# MT32Pi_Main.net
KiCad netlist of a schematic drawn in Altium Designer
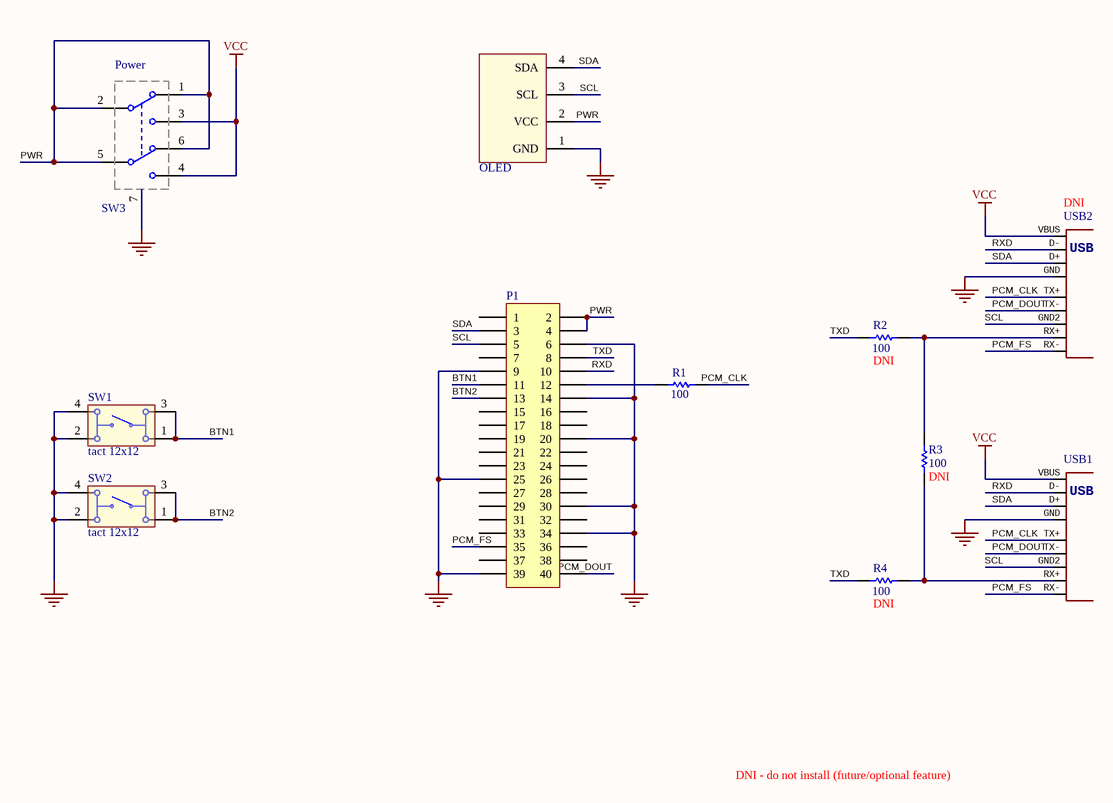
[diagram p0: MT32Pi_Main.SchDoc]

(export (version "E")
  (design (tool "Eeschema 10.0.6"))
  (components
    (comp (ref "OLED")
      (value "OLED")
      (footprint "OLED_128x64")
      (description "OLED 128x84 0.96\"")
      (libsource (lib "lib") (part "OLED"))
    )
    (comp (ref "P1")
      (value "Header 20X2")
      (footprint "HDR20x2")
      (description "Header, 20-Pin, Dual row")
      (fields (field (name "PUBLISHER") "Altium Limited"))
      (libsource (lib "Miscellaneous Connectors") (part "Header 20X2"))
    )
    (comp (ref "R1")
      (value "100")
      (footprint "R0805")
      (fields (field (name "PUBLISHER") "Altium Limited"))
      (libsource (lib "lib") (part "R0805"))
    )
    (comp (ref "R2")
      (value "100")
      (footprint "R0805 - DNI")
      (fields (field (name "PUBLISHER") "Altium Limited"))
      (libsource (lib "lib") (part "R0805 - DNI"))
    )
    (comp (ref "R3")
      (value "100")
      (footprint "R0805 - DNI")
      (fields (field (name "PUBLISHER") "Altium Limited"))
      (libsource (lib "lib") (part "R0805 - DNI"))
    )
    (comp (ref "R4")
      (value "100")
      (footprint "R0805 - DNI")
      (fields (field (name "PUBLISHER") "Altium Limited"))
      (libsource (lib "lib") (part "R0805 - DNI"))
    )
    (comp (ref "SW1")
      (value "tact 12x12")
      (footprint "tact 12x12")
      (libsource (lib "lib") (part "tact 12x12"))
    )
    (comp (ref "SW2")
      (value "tact 12x12")
      (footprint "tact 12x12")
      (libsource (lib "lib") (part "tact 12x12"))
    )
    (comp (ref "SW3") (value "Power") (footprint "SW DPDT") (libsource (lib "lib") (part "SW DPDT")))
    (comp (ref "USB1")
      (value "USBA30-PTH")
      (footprint "USB3-A-F-PTH")
      (fields (field (name "USB") "USB"))
      (libsource (lib "lib") (part "USBA30-PTH"))
    )
    (comp (ref "USB2")
      (value "USBA30-PTH")
      (footprint "USB3-A-F-PTH")
      (fields (field (name "USB") "USB"))
      (libsource (lib "lib") (part "USBA30-PTH"))
    )
  )
  (nets
    (net (code "1") (name "/BTN1") (class "Default")
      (node (ref "P1") (pin "11") (pinfunction "11_11") (pintype "passive"))
      (node (ref "SW1") (pin "1") (pinfunction "1_1") (pintype "passive"))
      (node (ref "SW1") (pin "3") (pinfunction "3_3") (pintype "passive"))
    )
    (net (code "2") (name "/BTN2") (class "Default")
      (node (ref "P1") (pin "13") (pinfunction "13_13") (pintype "passive"))
      (node (ref "SW2") (pin "1") (pinfunction "1_1") (pintype "passive"))
      (node (ref "SW2") (pin "3") (pinfunction "3_3") (pintype "passive"))
    )
    (net (code "3") (name "/PCM_CLK") (class "Default")
      (node (ref "R1") (pin "1") (pinfunction "1_1") (pintype "passive"))
      (node (ref "USB1") (pin "TX+") (pinfunction "TX+_TX+") (pintype "passive"))
      (node (ref "USB2") (pin "TX+") (pinfunction "TX+_TX+") (pintype "passive"))
    )
    (net (code "4") (name "/PCM_DOUT") (class "Default")
      (node (ref "P1") (pin "40") (pinfunction "40_40") (pintype "passive"))
      (node (ref "USB1") (pin "TX-") (pinfunction "TX-_TX-") (pintype "passive"))
      (node (ref "USB2") (pin "TX-") (pinfunction "TX-_TX-") (pintype "passive"))
    )
    (net (code "5") (name "/PCM_FS") (class "Default")
      (node (ref "P1") (pin "35") (pinfunction "35_35") (pintype "passive"))
      (node (ref "USB1") (pin "RX-") (pinfunction "RX-_RX-") (pintype "passive"))
      (node (ref "USB2") (pin "RX-") (pinfunction "RX-_RX-") (pintype "passive"))
    )
    (net (code "6") (name "/PWR") (class "Default")
      (node (ref "OLED") (pin "2") (pinfunction "VCC_2") (pintype "passive"))
      (node (ref "P1") (pin "2") (pinfunction "2_2") (pintype "passive"))
      (node (ref "P1") (pin "4") (pinfunction "4_4") (pintype "passive"))
      (node (ref "SW3") (pin "1") (pinfunction "NC1_1") (pintype "passive"))
      (node (ref "SW3") (pin "2") (pinfunction "COMMON1_2") (pintype "passive"))
      (node (ref "SW3") (pin "5") (pinfunction "COMMON2_5") (pintype "passive"))
      (node (ref "SW3") (pin "6") (pinfunction "NC2_6") (pintype "passive"))
    )
    (net (code "7") (name "/RXD") (class "Default")
      (node (ref "P1") (pin "10") (pinfunction "10_10") (pintype "passive"))
      (node (ref "USB1") (pin "D-") (pinfunction "D-_D-") (pintype "passive"))
      (node (ref "USB2") (pin "D-") (pinfunction "D-_D-") (pintype "passive"))
    )
    (net (code "8") (name "/SCL") (class "Default")
      (node (ref "OLED") (pin "3") (pinfunction "SCL_3") (pintype "passive"))
      (node (ref "P1") (pin "5") (pinfunction "5_5") (pintype "passive"))
      (node (ref "USB1") (pin "GND2") (pinfunction "GND2_GND2") (pintype "passive"))
      (node (ref "USB2") (pin "GND2") (pinfunction "GND2_GND2") (pintype "passive"))
    )
    (net (code "9") (name "/SDA") (class "Default")
      (node (ref "OLED") (pin "4") (pinfunction "SDA_4") (pintype "passive"))
      (node (ref "P1") (pin "3") (pinfunction "3_3") (pintype "passive"))
      (node (ref "USB1") (pin "D+") (pinfunction "D+_D+") (pintype "passive"))
      (node (ref "USB2") (pin "D+") (pinfunction "D+_D+") (pintype "passive"))
    )
    (net (code "10") (name "/TXD") (class "Default")
      (node (ref "P1") (pin "8") (pinfunction "8_8") (pintype "passive"))
      (node (ref "R2") (pin "1") (pinfunction "1_1") (pintype "passive"))
      (node (ref "R4") (pin "1") (pinfunction "1_1") (pintype "passive"))
    )
    (net (code "11") (name "GND") (class "Default")
      (node (ref "OLED") (pin "1") (pinfunction "GND_1") (pintype "passive"))
      (node (ref "P1") (pin "14") (pinfunction "14_14") (pintype "passive"))
      (node (ref "P1") (pin "20") (pinfunction "20_20") (pintype "passive"))
      (node (ref "P1") (pin "25") (pinfunction "25_25") (pintype "passive"))
      (node (ref "P1") (pin "30") (pinfunction "30_30") (pintype "passive"))
      (node (ref "P1") (pin "34") (pinfunction "34_34") (pintype "passive"))
      (node (ref "P1") (pin "39") (pinfunction "39_39") (pintype "passive"))
      (node (ref "P1") (pin "6") (pinfunction "6_6") (pintype "passive"))
      (node (ref "P1") (pin "9") (pinfunction "9_9") (pintype "passive"))
      (node (ref "SW1") (pin "2") (pinfunction "2_2") (pintype "passive"))
      (node (ref "SW1") (pin "4") (pinfunction "4_4") (pintype "passive"))
      (node (ref "SW2") (pin "2") (pinfunction "2_2") (pintype "passive"))
      (node (ref "SW2") (pin "4") (pinfunction "4_4") (pintype "passive"))
      (node (ref "SW3") (pin "7") (pinfunction "7_7") (pintype "passive"))
      (node (ref "USB1") (pin "GND") (pinfunction "GND_GND") (pintype "passive"))
      (node (ref "USB2") (pin "GND") (pinfunction "GND_GND") (pintype "passive"))
    )
    (net (code "12") (name "Net-(P1-Pad12)") (class "Default")
      (node (ref "P1") (pin "12") (pinfunction "12_12") (pintype "passive"))
      (node (ref "R1") (pin "2") (pinfunction "2_2") (pintype "passive"))
    )
    (net (code "13") (name "Net-(R2-Pad2)") (class "Default")
      (node (ref "R2") (pin "2") (pinfunction "2_2") (pintype "passive"))
      (node (ref "R3") (pin "2") (pinfunction "2_2") (pintype "passive"))
      (node (ref "USB2") (pin "RX+") (pinfunction "RX+_RX+") (pintype "passive"))
    )
    (net (code "14") (name "Net-(R3-Pad1)") (class "Default")
      (node (ref "R3") (pin "1") (pinfunction "1_1") (pintype "passive"))
      (node (ref "R4") (pin "2") (pinfunction "2_2") (pintype "passive"))
      (node (ref "USB1") (pin "RX+") (pinfunction "RX+_RX+") (pintype "passive"))
    )
    (net (code "15") (name "VCC") (class "Default")
      (node (ref "SW3") (pin "3") (pinfunction "NO1_3") (pintype "passive"))
      (node (ref "SW3") (pin "4") (pinfunction "NO2_4") (pintype "passive"))
      (node (ref "USB1") (pin "VBUS") (pinfunction "VBUS_VBUS") (pintype "passive"))
      (node (ref "USB2") (pin "VBUS") (pinfunction "VBUS_VBUS") (pintype "passive"))
    )
    (net (code "16") (name "unconnected-(P1-Pad1)") (class "Default")
      (node (ref "P1") (pin "1") (pinfunction "1_1") (pintype "passive"))
    )
    (net (code "17") (name "unconnected-(P1-Pad7)") (class "Default")
      (node (ref "P1") (pin "7") (pinfunction "7_7") (pintype "passive"))
    )
    (net (code "18") (name "unconnected-(P1-Pad15)") (class "Default")
      (node (ref "P1") (pin "15") (pinfunction "15_15") (pintype "passive"))
    )
    (net (code "19") (name "unconnected-(P1-Pad16)") (class "Default")
      (node (ref "P1") (pin "16") (pinfunction "16_16") (pintype "passive"))
    )
    (net (code "20") (name "unconnected-(P1-Pad17)") (class "Default")
      (node (ref "P1") (pin "17") (pinfunction "17_17") (pintype "passive"))
    )
    (net (code "21") (name "unconnected-(P1-Pad18)") (class "Default")
      (node (ref "P1") (pin "18") (pinfunction "18_18") (pintype "passive"))
    )
    (net (code "22") (name "unconnected-(P1-Pad19)") (class "Default")
      (node (ref "P1") (pin "19") (pinfunction "19_19") (pintype "passive"))
    )
    (net (code "23") (name "unconnected-(P1-Pad21)") (class "Default")
      (node (ref "P1") (pin "21") (pinfunction "21_21") (pintype "passive"))
    )
    (net (code "24") (name "unconnected-(P1-Pad22)") (class "Default")
      (node (ref "P1") (pin "22") (pinfunction "22_22") (pintype "passive"))
    )
    (net (code "25") (name "unconnected-(P1-Pad23)") (class "Default")
      (node (ref "P1") (pin "23") (pinfunction "23_23") (pintype "passive"))
    )
    (net (code "26") (name "unconnected-(P1-Pad24)") (class "Default")
      (node (ref "P1") (pin "24") (pinfunction "24_24") (pintype "passive"))
    )
    (net (code "27") (name "unconnected-(P1-Pad26)") (class "Default")
      (node (ref "P1") (pin "26") (pinfunction "26_26") (pintype "passive"))
    )
    (net (code "28") (name "unconnected-(P1-Pad27)") (class "Default")
      (node (ref "P1") (pin "27") (pinfunction "27_27") (pintype "passive"))
    )
    (net (code "29") (name "unconnected-(P1-Pad28)") (class "Default")
      (node (ref "P1") (pin "28") (pinfunction "28_28") (pintype "passive"))
    )
    (net (code "30") (name "unconnected-(P1-Pad29)") (class "Default")
      (node (ref "P1") (pin "29") (pinfunction "29_29") (pintype "passive"))
    )
    (net (code "31") (name "unconnected-(P1-Pad31)") (class "Default")
      (node (ref "P1") (pin "31") (pinfunction "31_31") (pintype "passive"))
    )
    (net (code "32") (name "unconnected-(P1-Pad32)") (class "Default")
      (node (ref "P1") (pin "32") (pinfunction "32_32") (pintype "passive"))
    )
    (net (code "33") (name "unconnected-(P1-Pad33)") (class "Default")
      (node (ref "P1") (pin "33") (pinfunction "33_33") (pintype "passive"))
    )
    (net (code "34") (name "unconnected-(P1-Pad36)") (class "Default")
      (node (ref "P1") (pin "36") (pinfunction "36_36") (pintype "passive"))
    )
    (net (code "35") (name "unconnected-(P1-Pad37)") (class "Default")
      (node (ref "P1") (pin "37") (pinfunction "37_37") (pintype "passive"))
    )
    (net (code "36") (name "unconnected-(P1-Pad38)") (class "Default")
      (node (ref "P1") (pin "38") (pinfunction "38_38") (pintype "passive"))
    )
  )
)
